# receiver-4x.net
KiCad netlist of a schematic drawn in EAGLE
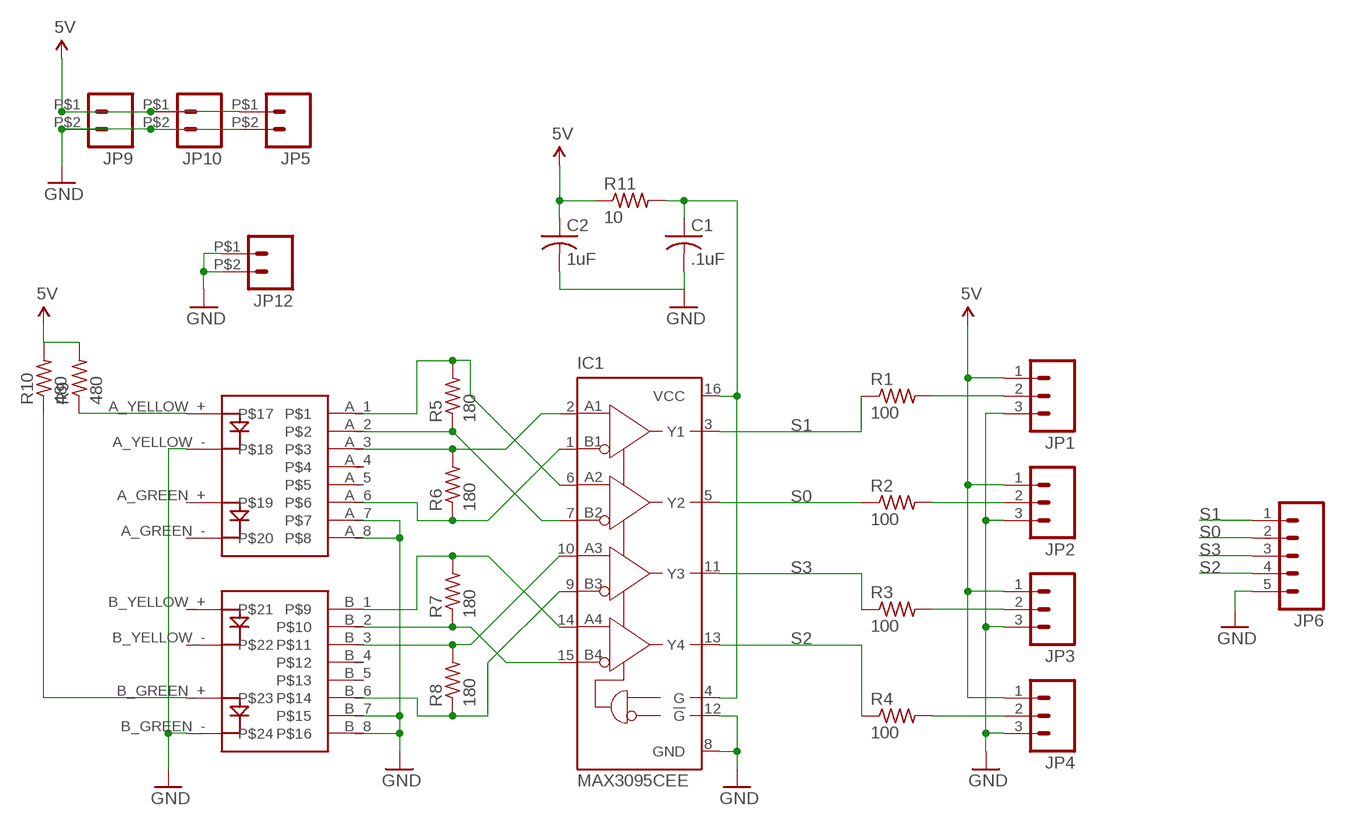
[diagram p0: schematic, sheet 1]

(export (version "E")
  (design (tool "Eeschema 10.0.6"))
  (components
    (comp (ref "C1")
      (value ".1uF")
      (footprint "eagle-import:C0603")
      (libsource (lib "eagle-import") (part "C-USC0603"))
    )
    (comp (ref "C2")
      (value "1uF")
      (footprint "eagle-import:C0603")
      (libsource (lib "eagle-import") (part "C-USC0603"))
    )
    (comp (ref "IC1")
      (value "MAX3095CEE")
      (footprint "eagle-import:QSOP16")
      (fields (field (name "MPN") "MAX3095CEE+"))
      (libsource (lib "eagle-import") (part "MAX309EE5C"))
    )
    (comp (ref "JP1")
      (value "M03SCREW-DETACH")
      (footprint "eagle-import:SCREWTERMINAL-5MM-3-DETACHABLE")
      (libsource (lib "eagle-import") (part "M03SCREW-DETACH"))
    )
    (comp (ref "JP2")
      (value "M03SCREW-DETACH")
      (footprint "eagle-import:SCREWTERMINAL-5MM-3-DETACHABLE")
      (libsource (lib "eagle-import") (part "M03SCREW-DETACH"))
    )
    (comp (ref "JP3")
      (value "M03SCREW-DETACH")
      (footprint "eagle-import:SCREWTERMINAL-5MM-3-DETACHABLE")
      (libsource (lib "eagle-import") (part "M03SCREW-DETACH"))
    )
    (comp (ref "JP4")
      (value "M03SCREW-DETACH")
      (footprint "eagle-import:SCREWTERMINAL-5MM-3-DETACHABLE")
      (libsource (lib "eagle-import") (part "M03SCREW-DETACH"))
    )
    (comp (ref "JP5")
      (value "M026.35MM")
      (footprint "eagle-import:SCREWTERMINAL-6.35MM-2")
      (libsource (lib "eagle-import") (part "M026.35MM"))
    )
    (comp (ref "JP6")
      (value "M05PTH")
      (footprint "eagle-import:1X05")
      (libsource (lib "eagle-import") (part "M05PTH"))
    )
    (comp (ref "JP9")
      (value "M026.35MM")
      (footprint "eagle-import:SCREWTERMINAL-6.35MM-2")
      (libsource (lib "eagle-import") (part "M026.35MM"))
    )
    (comp (ref "JP10")
      (value "M026.35MM")
      (footprint "eagle-import:SCREWTERMINAL-6.35MM-2")
      (libsource (lib "eagle-import") (part "M026.35MM"))
    )
    (comp (ref "JP12")
      (value "M026.35MM")
      (footprint "eagle-import:SCREWTERMINAL-6.35MM-2")
      (libsource (lib "eagle-import") (part "M026.35MM"))
    )
    (comp (ref "R1")
      (value "100")
      (footprint "eagle-import:R0603")
      (libsource (lib "eagle-import") (part "R-US_R0603"))
    )
    (comp (ref "R2")
      (value "100")
      (footprint "eagle-import:R0603")
      (libsource (lib "eagle-import") (part "R-US_R0603"))
    )
    (comp (ref "R3")
      (value "100")
      (footprint "eagle-import:R0603")
      (libsource (lib "eagle-import") (part "R-US_R0603"))
    )
    (comp (ref "R4")
      (value "100")
      (footprint "eagle-import:R0603")
      (libsource (lib "eagle-import") (part "R-US_R0603"))
    )
    (comp (ref "R5")
      (value "180")
      (footprint "eagle-import:R0603")
      (libsource (lib "eagle-import") (part "R-US_R0603"))
    )
    (comp (ref "R6")
      (value "180")
      (footprint "eagle-import:R0603")
      (libsource (lib "eagle-import") (part "R-US_R0603"))
    )
    (comp (ref "R7")
      (value "180")
      (footprint "eagle-import:R0603")
      (libsource (lib "eagle-import") (part "R-US_R0603"))
    )
    (comp (ref "R8")
      (value "180")
      (footprint "eagle-import:R0603")
      (libsource (lib "eagle-import") (part "R-US_R0603"))
    )
    (comp (ref "R9")
      (value "480")
      (footprint "eagle-import:R0603")
      (libsource (lib "eagle-import") (part "R-US_R0603"))
    )
    (comp (ref "R10")
      (value "480")
      (footprint "eagle-import:R0603")
      (libsource (lib "eagle-import") (part "R-US_R0603"))
    )
    (comp (ref "R11")
      (value "10")
      (footprint "eagle-import:R0603")
      (libsource (lib "eagle-import") (part "R-US_R0603"))
    )
    (comp (ref "U$1")
      (value "RJ45_2X1")
      (footprint "eagle-import:RJ45_2X1")
      (libsource (lib "eagle-import") (part "RJ45_2X1"))
    )
  )
  (nets
    (net (code "1") (name "/S0") (class "Default")
      (node (ref "IC1") (pin "5") (pinfunction "Y2_5") (pintype "output"))
      (node (ref "JP6") (pin "2") (pinfunction "2_2") (pintype "passive"))
      (node (ref "R2") (pin "1") (pinfunction "1_1") (pintype "passive"))
    )
    (net (code "2") (name "/S1") (class "Default")
      (node (ref "IC1") (pin "3") (pinfunction "Y1_3") (pintype "output"))
      (node (ref "JP6") (pin "1") (pinfunction "1_1") (pintype "passive"))
      (node (ref "R1") (pin "1") (pinfunction "1_1") (pintype "passive"))
    )
    (net (code "3") (name "/S2") (class "Default")
      (node (ref "IC1") (pin "13") (pinfunction "Y4_13") (pintype "output"))
      (node (ref "JP6") (pin "4") (pinfunction "4_4") (pintype "passive"))
      (node (ref "R4") (pin "1") (pinfunction "1_1") (pintype "passive"))
    )
    (net (code "4") (name "/S3") (class "Default")
      (node (ref "IC1") (pin "11") (pinfunction "Y3_11") (pintype "output"))
      (node (ref "JP6") (pin "3") (pinfunction "3_3") (pintype "passive"))
      (node (ref "R3") (pin "1") (pinfunction "1_1") (pintype "passive"))
    )
    (net (code "5") (name "5V") (class "Default")
      (node (ref "C2") (pin "1") (pinfunction "1_1") (pintype "passive"))
      (node (ref "JP1") (pin "1") (pinfunction "1_1") (pintype "passive"))
      (node (ref "JP10") (pin "P$1") (pinfunction "1_P$1") (pintype "passive"))
      (node (ref "JP2") (pin "1") (pinfunction "1_1") (pintype "passive"))
      (node (ref "JP3") (pin "1") (pinfunction "1_1") (pintype "passive"))
      (node (ref "JP4") (pin "1") (pinfunction "1_1") (pintype "passive"))
      (node (ref "JP5") (pin "P$1") (pinfunction "1_P$1") (pintype "passive"))
      (node (ref "JP9") (pin "P$1") (pinfunction "1_P$1") (pintype "passive"))
      (node (ref "R10") (pin "2") (pinfunction "2_2") (pintype "passive"))
      (node (ref "R11") (pin "1") (pinfunction "1_1") (pintype "passive"))
      (node (ref "R9") (pin "2") (pinfunction "2_2") (pintype "passive"))
    )
    (net (code "6") (name "GND") (class "Default")
      (node (ref "C1") (pin "2") (pinfunction "2_2") (pintype "passive"))
      (node (ref "C2") (pin "2") (pinfunction "2_2") (pintype "passive"))
      (node (ref "IC1") (pin "12") (pinfunction "~{G}_12") (pintype "input"))
      (node (ref "IC1") (pin "8") (pinfunction "GND_8") (pintype "power_in"))
      (node (ref "JP1") (pin "3") (pinfunction "3_3") (pintype "passive"))
      (node (ref "JP10") (pin "P$2") (pinfunction "2_P$2") (pintype "passive"))
      (node (ref "JP12") (pin "P$1") (pinfunction "1_P$1") (pintype "passive"))
      (node (ref "JP12") (pin "P$2") (pinfunction "2_P$2") (pintype "passive"))
      (node (ref "JP2") (pin "3") (pinfunction "3_3") (pintype "passive"))
      (node (ref "JP3") (pin "3") (pinfunction "3_3") (pintype "passive"))
      (node (ref "JP4") (pin "3") (pinfunction "3_3") (pintype "passive"))
      (node (ref "JP5") (pin "P$2") (pinfunction "2_P$2") (pintype "passive"))
      (node (ref "JP6") (pin "5") (pinfunction "5_5") (pintype "passive"))
      (node (ref "JP9") (pin "P$2") (pinfunction "2_P$2") (pintype "passive"))
      (node (ref "U$1") (pin "A_7") (pinfunction "P$7_A_7") (pintype "bidirectional"))
      (node (ref "U$1") (pin "A_8") (pinfunction "P$8_A_8") (pintype "bidirectional"))
      (node (ref "U$1") (pin "A_YELLOW_-") (pinfunction "P$18_A_YELLOW_-") (pintype "bidirectional"))
      (node (ref "U$1") (pin "B_7") (pinfunction "P$15_B_7") (pintype "bidirectional"))
      (node (ref "U$1") (pin "B_8") (pinfunction "P$16_B_8") (pintype "bidirectional"))
      (node (ref "U$1") (pin "B_GREEN_-") (pinfunction "P$24_B_GREEN_-") (pintype "bidirectional"))
    )
    (net (code "7") (name "Net-(IC1-A1)") (class "Default")
      (node (ref "IC1") (pin "2") (pinfunction "A1_2") (pintype "input"))
      (node (ref "R6") (pin "2") (pinfunction "2_2") (pintype "passive"))
      (node (ref "U$1") (pin "A_3") (pinfunction "P$3_A_3") (pintype "bidirectional"))
    )
    (net (code "8") (name "Net-(IC1-A2)") (class "Default")
      (node (ref "IC1") (pin "6") (pinfunction "A2_6") (pintype "input"))
      (node (ref "R5") (pin "2") (pinfunction "2_2") (pintype "passive"))
      (node (ref "U$1") (pin "A_1") (pinfunction "P$1_A_1") (pintype "bidirectional"))
    )
    (net (code "9") (name "Net-(IC1-A3)") (class "Default")
      (node (ref "IC1") (pin "10") (pinfunction "A3_10") (pintype "input"))
      (node (ref "R8") (pin "2") (pinfunction "2_2") (pintype "passive"))
      (node (ref "U$1") (pin "B_3") (pinfunction "P$11_B_3") (pintype "bidirectional"))
    )
    (net (code "10") (name "Net-(IC1-A4)") (class "Default")
      (node (ref "IC1") (pin "14") (pinfunction "A4_14") (pintype "input"))
      (node (ref "R7") (pin "2") (pinfunction "2_2") (pintype "passive"))
      (node (ref "U$1") (pin "B_1") (pinfunction "P$9_B_1") (pintype "bidirectional"))
    )
    (net (code "11") (name "Net-(IC1-B1)") (class "Default")
      (node (ref "IC1") (pin "1") (pinfunction "B1_1") (pintype "input"))
      (node (ref "R6") (pin "1") (pinfunction "1_1") (pintype "passive"))
      (node (ref "U$1") (pin "A_6") (pinfunction "P$6_A_6") (pintype "bidirectional"))
    )
    (net (code "12") (name "Net-(IC1-B2)") (class "Default")
      (node (ref "IC1") (pin "7") (pinfunction "B2_7") (pintype "input"))
      (node (ref "R5") (pin "1") (pinfunction "1_1") (pintype "passive"))
      (node (ref "U$1") (pin "A_2") (pinfunction "P$2_A_2") (pintype "bidirectional"))
    )
    (net (code "13") (name "Net-(IC1-B3)") (class "Default")
      (node (ref "IC1") (pin "9") (pinfunction "B3_9") (pintype "input"))
      (node (ref "R8") (pin "1") (pinfunction "1_1") (pintype "passive"))
      (node (ref "U$1") (pin "B_6") (pinfunction "P$14_B_6") (pintype "bidirectional"))
    )
    (net (code "14") (name "Net-(IC1-B4)") (class "Default")
      (node (ref "IC1") (pin "15") (pinfunction "B4_15") (pintype "input"))
      (node (ref "R7") (pin "1") (pinfunction "1_1") (pintype "passive"))
      (node (ref "U$1") (pin "B_2") (pinfunction "P$10_B_2") (pintype "bidirectional"))
    )
    (net (code "15") (name "Net-(IC1-G)") (class "Default")
      (node (ref "C1") (pin "1") (pinfunction "1_1") (pintype "passive"))
      (node (ref "IC1") (pin "16") (pinfunction "VCC_16") (pintype "power_in"))
      (node (ref "IC1") (pin "4") (pinfunction "G_4") (pintype "input"))
      (node (ref "R11") (pin "2") (pinfunction "2_2") (pintype "passive"))
    )
    (net (code "16") (name "Net-(JP1-Pad2)") (class "Default")
      (node (ref "JP1") (pin "2") (pinfunction "2_2") (pintype "passive"))
      (node (ref "R1") (pin "2") (pinfunction "2_2") (pintype "passive"))
    )
    (net (code "17") (name "Net-(JP2-Pad2)") (class "Default")
      (node (ref "JP2") (pin "2") (pinfunction "2_2") (pintype "passive"))
      (node (ref "R2") (pin "2") (pinfunction "2_2") (pintype "passive"))
    )
    (net (code "18") (name "Net-(JP3-Pad2)") (class "Default")
      (node (ref "JP3") (pin "2") (pinfunction "2_2") (pintype "passive"))
      (node (ref "R3") (pin "2") (pinfunction "2_2") (pintype "passive"))
    )
    (net (code "19") (name "Net-(JP4-Pad2)") (class "Default")
      (node (ref "JP4") (pin "2") (pinfunction "2_2") (pintype "passive"))
      (node (ref "R4") (pin "2") (pinfunction "2_2") (pintype "passive"))
    )
    (net (code "20") (name "Net-(U$1-P$17)") (class "Default")
      (node (ref "R9") (pin "1") (pinfunction "1_1") (pintype "passive"))
      (node (ref "U$1") (pin "A_YELLOW_+") (pinfunction "P$17_A_YELLOW_+") (pintype "bidirectional"))
    )
    (net (code "21") (name "Net-(U$1-P$23)") (class "Default")
      (node (ref "R10") (pin "1") (pinfunction "1_1") (pintype "passive"))
      (node (ref "U$1") (pin "B_GREEN_+") (pinfunction "P$23_B_GREEN_+") (pintype "bidirectional"))
    )
    (net (code "22") (name "unconnected-(U$1-P$4-PadA_4)") (class "Default")
      (node (ref "U$1") (pin "A_4") (pinfunction "P$4_A_4") (pintype "bidirectional"))
    )
    (net (code "23") (name "unconnected-(U$1-P$5-PadA_5)") (class "Default")
      (node (ref "U$1") (pin "A_5") (pinfunction "P$5_A_5") (pintype "bidirectional"))
    )
    (net (code "24") (name "unconnected-(U$1-P$12-PadB_4)") (class "Default")
      (node (ref "U$1") (pin "B_4") (pinfunction "P$12_B_4") (pintype "bidirectional"))
    )
    (net (code "25") (name "unconnected-(U$1-P$13-PadB_5)") (class "Default")
      (node (ref "U$1") (pin "B_5") (pinfunction "P$13_B_5") (pintype "bidirectional"))
    )
    (net (code "26") (name "unconnected-(U$1-P$19-PadA_GREEN_+)") (class "Default")
      (node (ref "U$1") (pin "A_GREEN_+") (pinfunction "P$19_A_GREEN_+") (pintype "bidirectional"))
    )
    (net (code "27") (name "unconnected-(U$1-P$20-PadA_GREEN_-)") (class "Default")
      (node (ref "U$1") (pin "A_GREEN_-") (pinfunction "P$20_A_GREEN_-") (pintype "bidirectional"))
    )
    (net (code "28") (name "unconnected-(U$1-P$21-PadB_YELLOW_+)") (class "Default")
      (node (ref "U$1") (pin "B_YELLOW_+") (pinfunction "P$21_B_YELLOW_+") (pintype "bidirectional"))
    )
    (net (code "29") (name "unconnected-(U$1-P$22-PadB_YELLOW_-)") (class "Default")
      (node (ref "U$1") (pin "B_YELLOW_-") (pinfunction "P$22_B_YELLOW_-") (pintype "bidirectional"))
    )
  )
)
